# 04_HMS_Output.net
KiCad netlist of a schematic drawn in Altium Designer
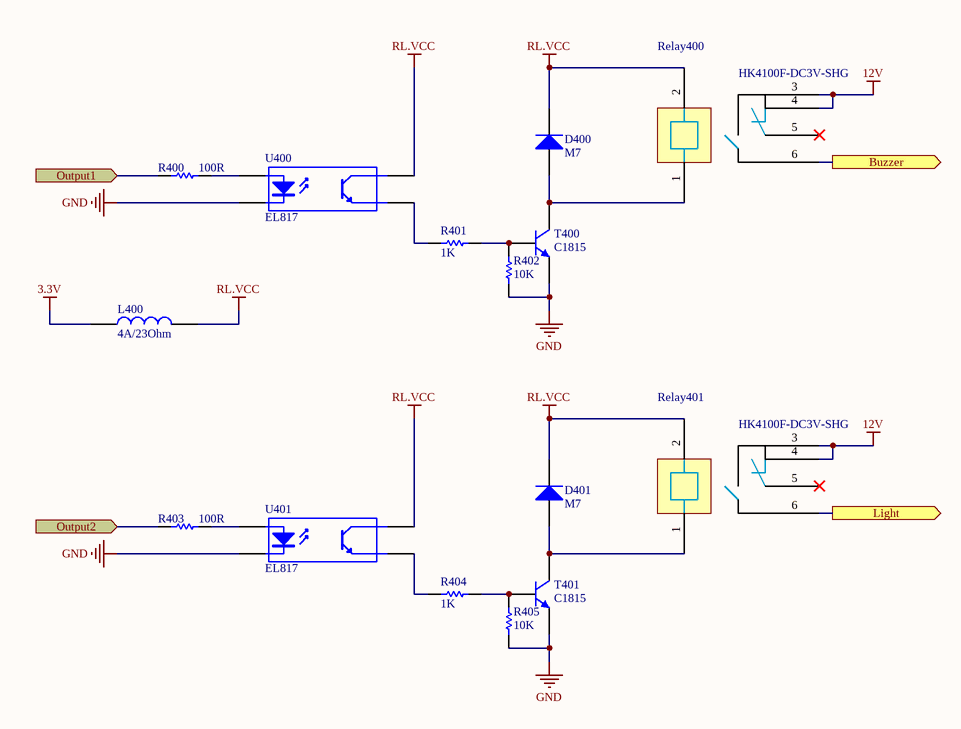
[diagram p0: [04].HMS.Output.SchDoc]

(export (version "E")
  (design (tool "Eeschema 10.0.6"))
  (components
    (comp (ref "D400")
      (value "M7")
      (footprint "DO214AC_SMA_1808")
      (description "Diode M7 - 1N4007")
      (fields (field (name "MPN") "1N4007 M7") (field (name "PUBLISHER") "Altium Limited"))
      (libsource (lib "04.Diode_Led") (part "Diode M7"))
    )
    (comp (ref "D401")
      (value "M7")
      (footprint "DO214AC_SMA_1808")
      (description "Diode M7 - 1N4007")
      (fields (field (name "MPN") "1N4007 M7") (field (name "PUBLISHER") "Altium Limited"))
      (libsource (lib "04.Diode_Led") (part "Diode M7"))
    )
    (comp (ref "L400")
      (value "4A/23Ohm")
      (footprint "Inductor_0603")
      (description "Inductor Ferrites 4A SMD 0603")
      (fields (field (name "MPN") "FBMJ1608HM230NT") (field (name "MFR") "Taiyo Yuden"))
      (libsource (lib "03.Inductor") (part "FBMJ1608HM230NT"))
    )
    (comp (ref "R400")
      (value "100R")
      (footprint "RES_0402(1005)")
      (description "RES 100 OHM 1% 1/8W 0402")
      (fields
        (field (name "MPN") "RC0402FR-7W100RL")
        (field (name "MFR") "YAGEO")
        (field (name "PUBLISHER") "Altium Limited")
      )
      (libsource (lib "Miscellaneous Devices") (part "Res1"))
    )
    (comp (ref "R401")
      (value "1K")
      (footprint "RES_0402(1005)")
      (description "RES 1K OHM 1% 1/8W 0402")
      (fields
        (field (name "MPN") "RC0402FR-071KL")
        (field (name "MFR") "YAGEO")
        (field (name "PUBLISHER") "Altium Limited")
      )
      (libsource (lib "Miscellaneous Devices") (part "Res1"))
    )
    (comp (ref "R402")
      (value "10K")
      (footprint "RES_0402(1005)")
      (description "RES 10K OHM 5% 1/8W 0402")
      (fields
        (field (name "MPN") "RC0402JR-0710KL")
        (field (name "MFR") "YAGEO")
        (field (name "PUBLISHER") "Altium Limited")
      )
      (libsource (lib "Miscellaneous Devices") (part "Res1"))
    )
    (comp (ref "R403")
      (value "100R")
      (footprint "RES_0402(1005)")
      (description "RES 100 OHM 1% 1/8W 0402")
      (fields
        (field (name "MPN") "RC0402FR-7W100RL")
        (field (name "MFR") "YAGEO")
        (field (name "PUBLISHER") "Altium Limited")
      )
      (libsource (lib "Miscellaneous Devices") (part "Res1"))
    )
    (comp (ref "R404")
      (value "1K")
      (footprint "RES_0402(1005)")
      (description "RES 1K OHM 1% 1/8W 0402")
      (fields
        (field (name "MPN") "RC0402FR-071KL")
        (field (name "MFR") "YAGEO")
        (field (name "PUBLISHER") "Altium Limited")
      )
      (libsource (lib "Miscellaneous Devices") (part "Res1"))
    )
    (comp (ref "R405")
      (value "10K")
      (footprint "RES_0402(1005)")
      (description "RES 10K OHM 5% 1/8W 0402")
      (fields
        (field (name "MPN") "RC0402JR-0710KL")
        (field (name "MFR") "YAGEO")
        (field (name "PUBLISHER") "Altium Limited")
      )
      (libsource (lib "Miscellaneous Devices") (part "Res1"))
    )
    (comp (ref "Relay400")
      (value "HK4100F-DC3V-SHG")
      (footprint "HK4001F")
      (description "HK4100F-DC3V-SHG Relay 3V 3A 6 chân")
      (fields (field (name "MFR") "OEM"))
      (libsource (lib "HMS.Fire.Alarm") (part "HK4100F"))
    )
    (comp (ref "Relay401")
      (value "HK4100F-DC3V-SHG")
      (footprint "HK4001F")
      (description "HK4100F-DC3V-SHG Relay 3V 3A 6 chân")
      (fields (field (name "MFR") "OEM"))
      (libsource (lib "HMS.Fire.Alarm") (part "HK4100F"))
    )
    (comp (ref "T400")
      (value "C1815")
      (footprint "SOT23-3")
      (description "Trans C1815 NPN 0.15A/50V SMD SOT23")
      (fields
        (field (name "MPN") "2SC1815")
        (field (name "MFR") "LinhKienChatLuong")
        (field (name "PUBLISHER") "Altium Limited")
      )
      (libsource (lib "Miscellaneous Devices") (part "2N3904"))
    )
    (comp (ref "T401")
      (value "C1815")
      (footprint "SOT23-3")
      (description "Trans C1815 NPN 0.15A/50V SMD SOT23")
      (fields
        (field (name "MPN") "2SC1815")
        (field (name "MFR") "LinhKienChatLuong")
        (field (name "PUBLISHER") "Altium Limited")
      )
      (libsource (lib "Miscellaneous Devices") (part "2N3904"))
    )
    (comp (ref "U400")
      (value "EL817")
      (footprint "Opto small")
      (description "Optoisolator Transistor Output 3750Vrms 1 Channel 4-SOP")
      (fields (field (name "MFR") "Vishay Semiconductor Opto Division"))
      (libsource (lib "*") (part "OPTOISO1"))
    )
    (comp (ref "U401")
      (value "EL817")
      (footprint "Opto small")
      (description "Optoisolator Transistor Output 3750Vrms 1 Channel 4-SOP")
      (fields (field (name "MFR") "Vishay Semiconductor Opto Division"))
      (libsource (lib "*") (part "OPTOISO1"))
    )
  )
  (nets
    (net (code "1") (name "/Buzzer") (class "Default")
      (node (ref "Relay400") (pin "6") (pinfunction "6_6") (pintype "passive"))
    )
    (net (code "2") (name "/Light") (class "Default")
      (node (ref "Relay401") (pin "6") (pinfunction "6_6") (pintype "passive"))
    )
    (net (code "3") (name "/Output1") (class "Default")
      (node (ref "R400") (pin "2") (pinfunction "2_2") (pintype "passive"))
    )
    (net (code "4") (name "/Output2") (class "Default")
      (node (ref "R403") (pin "2") (pinfunction "2_2") (pintype "passive"))
    )
    (net (code "5") (name "3.3V") (class "Default")
      (node (ref "L400") (pin "1") (pinfunction "1_1") (pintype "passive"))
    )
    (net (code "6") (name "12V") (class "Default")
      (node (ref "Relay400") (pin "3") (pinfunction "3_3") (pintype "passive"))
      (node (ref "Relay400") (pin "4") (pinfunction "4_4") (pintype "passive"))
      (node (ref "Relay401") (pin "3") (pinfunction "3_3") (pintype "passive"))
      (node (ref "Relay401") (pin "4") (pinfunction "4_4") (pintype "passive"))
    )
    (net (code "7") (name "GND") (class "Default")
      (node (ref "R402") (pin "1") (pinfunction "1_1") (pintype "passive"))
      (node (ref "R405") (pin "1") (pinfunction "1_1") (pintype "passive"))
      (node (ref "T400") (pin "2") (pinfunction "E_2") (pintype "passive"))
      (node (ref "T401") (pin "2") (pinfunction "E_2") (pintype "passive"))
      (node (ref "U400") (pin "2") (pinfunction "2_2") (pintype "passive"))
      (node (ref "U401") (pin "2") (pinfunction "2_2") (pintype "passive"))
    )
    (net (code "8") (name "Net-(D400-A)") (class "Default")
      (node (ref "D400") (pin "1") (pinfunction "A_1") (pintype "passive"))
      (node (ref "Relay400") (pin "1") (pinfunction "1_1") (pintype "passive"))
      (node (ref "T400") (pin "3") (pinfunction "C_3") (pintype "passive"))
    )
    (net (code "9") (name "Net-(D401-A)") (class "Default")
      (node (ref "D401") (pin "1") (pinfunction "A_1") (pintype "passive"))
      (node (ref "Relay401") (pin "1") (pinfunction "1_1") (pintype "passive"))
      (node (ref "T401") (pin "3") (pinfunction "C_3") (pintype "passive"))
    )
    (net (code "10") (name "Net-(R400-Pad1)") (class "Default")
      (node (ref "R400") (pin "1") (pinfunction "1_1") (pintype "passive"))
      (node (ref "U400") (pin "1") (pinfunction "1_1") (pintype "passive"))
    )
    (net (code "11") (name "Net-(R401-Pad2)") (class "Default")
      (node (ref "R401") (pin "2") (pinfunction "2_2") (pintype "passive"))
      (node (ref "U400") (pin "3") (pinfunction "3_3") (pintype "passive"))
    )
    (net (code "12") (name "Net-(R403-Pad1)") (class "Default")
      (node (ref "R403") (pin "1") (pinfunction "1_1") (pintype "passive"))
      (node (ref "U401") (pin "1") (pinfunction "1_1") (pintype "passive"))
    )
    (net (code "13") (name "Net-(R404-Pad2)") (class "Default")
      (node (ref "R404") (pin "2") (pinfunction "2_2") (pintype "passive"))
      (node (ref "U401") (pin "3") (pinfunction "3_3") (pintype "passive"))
    )
    (net (code "14") (name "Net-(T400-B)") (class "Default")
      (node (ref "R401") (pin "1") (pinfunction "1_1") (pintype "passive"))
      (node (ref "R402") (pin "2") (pinfunction "2_2") (pintype "passive"))
      (node (ref "T400") (pin "1") (pinfunction "B_1") (pintype "passive"))
    )
    (net (code "15") (name "Net-(T401-B)") (class "Default")
      (node (ref "R404") (pin "1") (pinfunction "1_1") (pintype "passive"))
      (node (ref "R405") (pin "2") (pinfunction "2_2") (pintype "passive"))
      (node (ref "T401") (pin "1") (pinfunction "B_1") (pintype "passive"))
    )
    (net (code "16") (name "RL.VCC") (class "Default")
      (node (ref "D400") (pin "2") (pinfunction "K_2") (pintype "passive"))
      (node (ref "D401") (pin "2") (pinfunction "K_2") (pintype "passive"))
      (node (ref "L400") (pin "2") (pinfunction "2_2") (pintype "passive"))
      (node (ref "Relay400") (pin "2") (pinfunction "2_2") (pintype "passive"))
      (node (ref "Relay401") (pin "2") (pinfunction "2_2") (pintype "passive"))
      (node (ref "U400") (pin "4") (pinfunction "4_4") (pintype "passive"))
      (node (ref "U401") (pin "4") (pinfunction "4_4") (pintype "passive"))
    )
    (net (code "17") (name "unconnected-(Relay400-Pad5)") (class "Default")
      (node (ref "Relay400") (pin "5") (pinfunction "5_5") (pintype "passive+no_connect"))
    )
    (net (code "18") (name "unconnected-(Relay401-Pad5)") (class "Default")
      (node (ref "Relay401") (pin "5") (pinfunction "5_5") (pintype "passive+no_connect"))
    )
  )
)
